# MySens-easyRS485-BluePill-V03-010.net
KiCad netlist of a schematic drawn in EAGLE
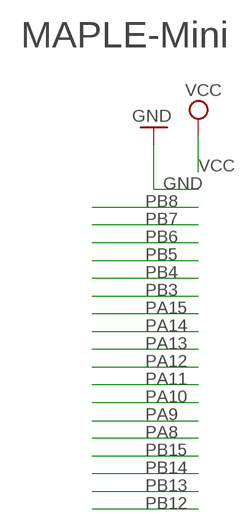
[diagram p0: schematic, sheet 1, part 1 of 2]
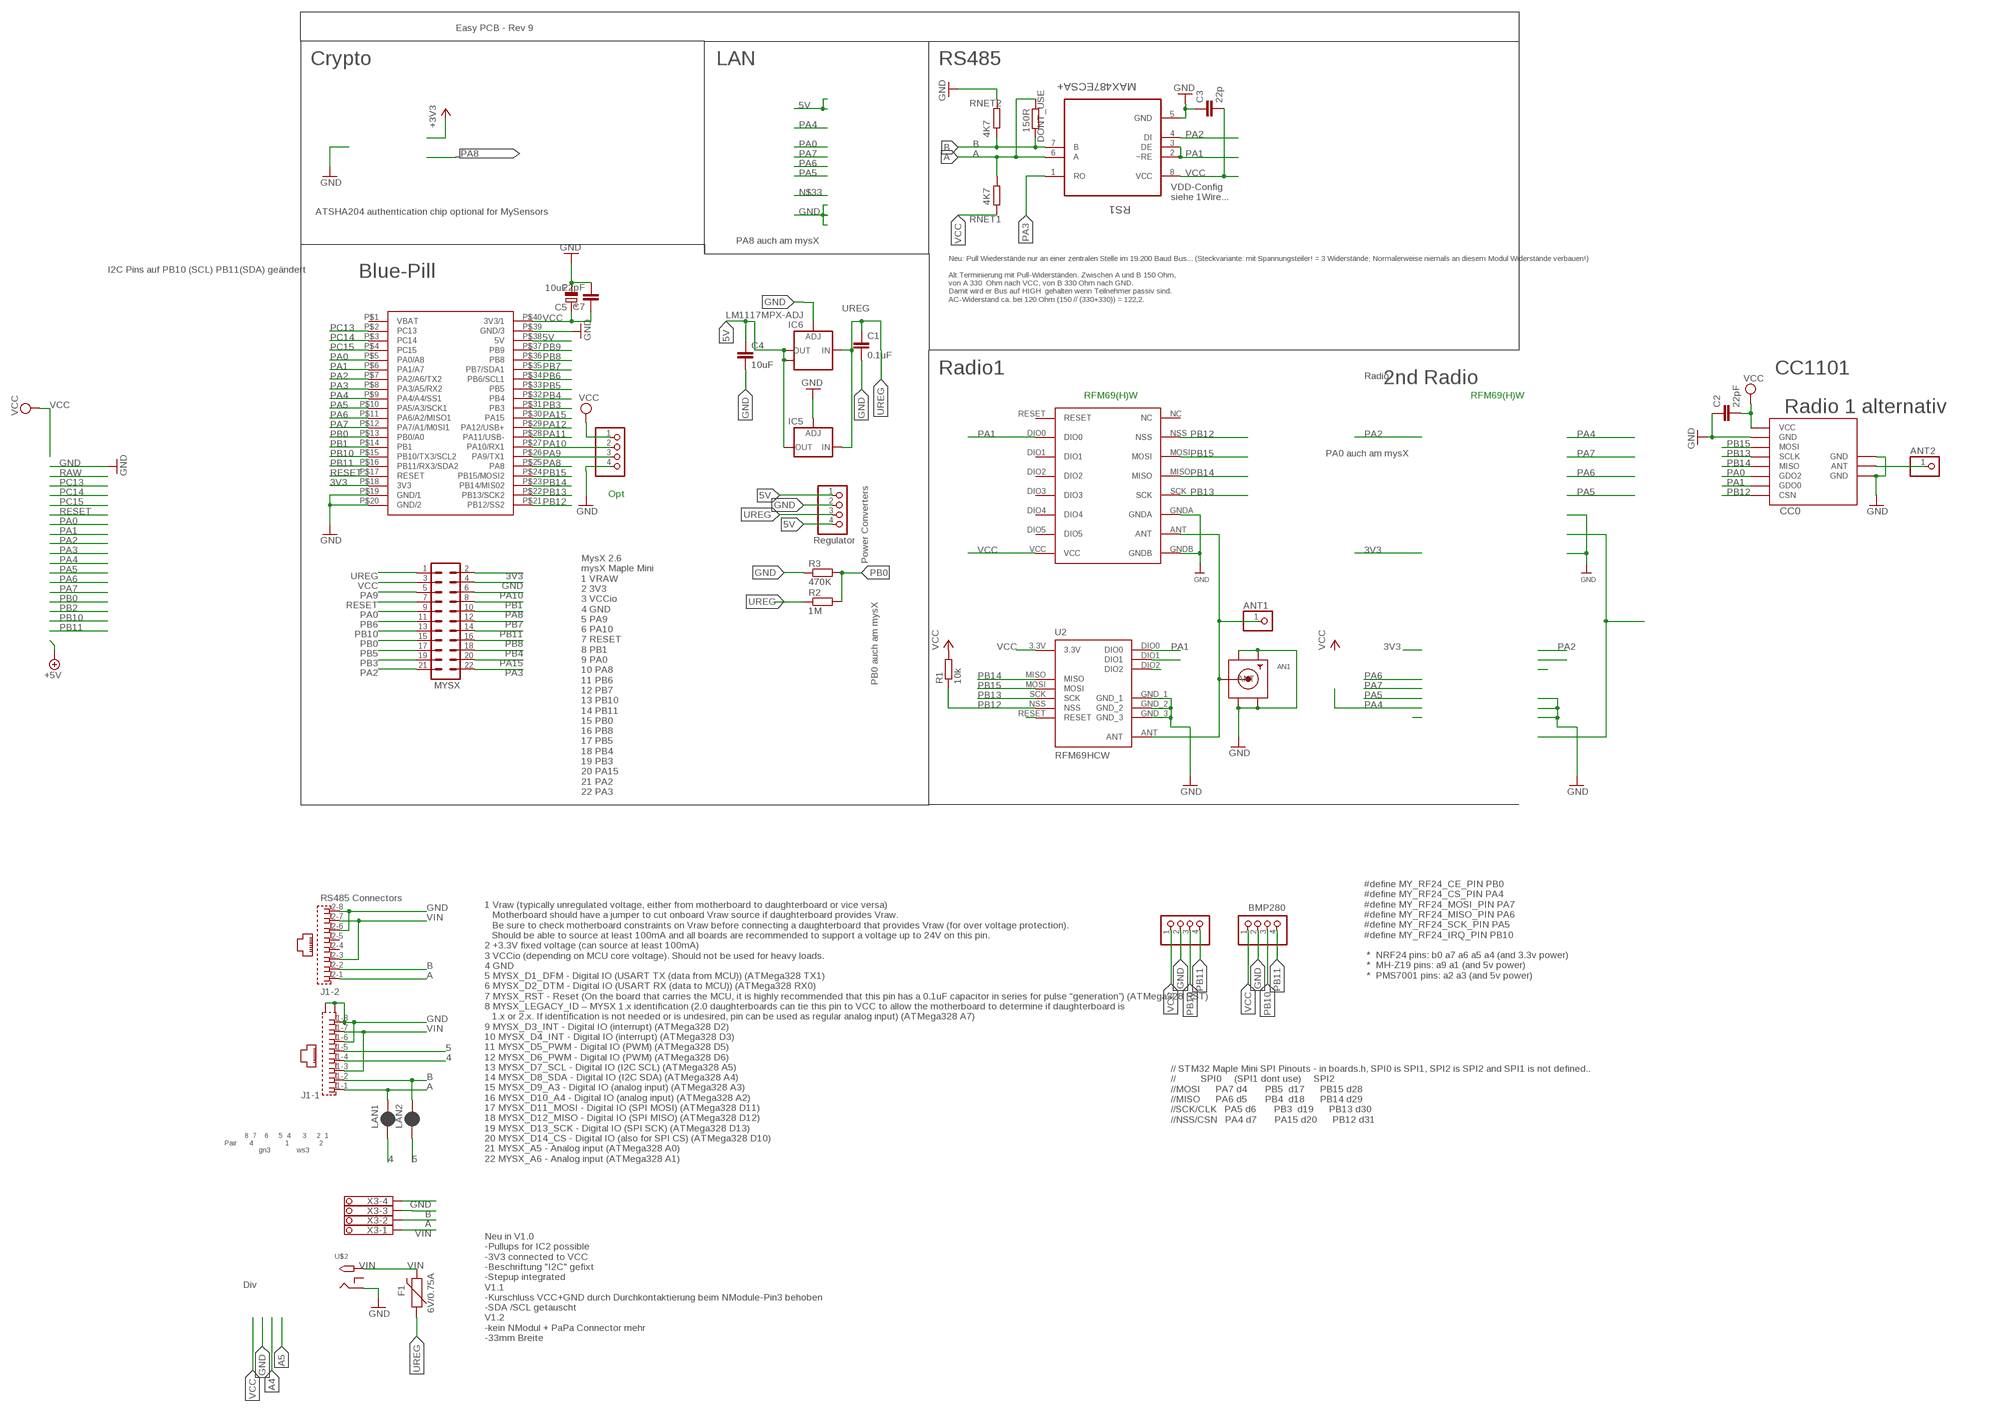
[diagram p1: schematic, sheet 1, part 2 of 2]

(export (version "E")
  (design (tool "Eeschema 10.0.6"))
  (components
    (comp (ref "AN1")
      (value "SMACONNECTOR_EDGE")
      (footprint "eagle-import:SMA_EDGELAUNCH")
      (libsource (lib "eagle-import") (part "SMACONNECTOR_EDGE"))
    )
    (comp (ref "ANT1")
      (value "PINHD-1X1")
      (footprint "eagle-import:1X01")
      (libsource (lib "eagle-import") (part "PINHD-1X1"))
    )
    (comp (ref "ANT2")
      (value "PINHD-1X1")
      (footprint "eagle-import:1X01")
      (libsource (lib "eagle-import") (part "PINHD-1X1"))
    )
    (comp (ref "BH1750")
      (value "PINHD-1X04_2.54-S")
      (footprint "eagle-import:1X04-S")
      (libsource (lib "eagle-import") (part "PINHD-1X04_2.54-S"))
    )
    (comp (ref "C1")
      (value "0.1uF")
      (footprint "eagle-import:C1206")
      (libsource (lib "eagle-import") (part "C-EUC1206"))
    )
    (comp (ref "C2")
      (value "22pF")
      (footprint "eagle-import:C0805")
      (libsource (lib "eagle-import") (part "C-EUC0805"))
    )
    (comp (ref "C3")
      (value "22p")
      (footprint "eagle-import:C0805")
      (libsource (lib "eagle-import") (part "C-EUC0805"))
    )
    (comp (ref "C4")
      (value "10uF")
      (footprint "eagle-import:C1210")
      (libsource (lib "eagle-import") (part "C-EUC1210"))
    )
    (comp (ref "C5")
      (value "10uF")
      (footprint "eagle-import:R_2012-12W")
      (libsource (lib "eagle-import") (part "CPOL-EUR/2012-12W"))
    )
    (comp (ref "C7")
      (value "22pF")
      (footprint "eagle-import:C0805")
      (libsource (lib "eagle-import") (part "C-EUC0805"))
    )
    (comp (ref "CC0")
      (value "CC1101")
      (footprint "eagle-import:CC1101_MODULE1_SMD")
      (libsource (lib "eagle-import") (part "CC1101_MODULE1SMD"))
    )
    (comp (ref "DBG")
      (value "PINHD-1X04_2.54-S")
      (footprint "eagle-import:1X04-S")
      (libsource (lib "eagle-import") (part "PINHD-1X04_2.54-S"))
    )
    (comp (ref "DONT_USE")
      (value "150R")
      (footprint "eagle-import:R0805")
      (libsource (lib "eagle-import") (part "R-EU_R0805"))
    )
    (comp (ref "F1")
      (value "6V/0.75A")
      (footprint "eagle-import:1206")
      (libsource (lib "eagle-import") (part "PPTC_THREE-QUARTER-AMP"))
    )
    (comp (ref "I2C-1")
      (value "PINHD-1X04_2.54-S")
      (footprint "eagle-import:1X04-S")
      (libsource (lib "eagle-import") (part "PINHD-1X04_2.54-S"))
    )
    (comp (ref "IC5")
      (value "LD117ADT50TR")
      (footprint "eagle-import:DPACK")
      (libsource (lib "eagle-import") (part "LD117A?DT50TR"))
    )
    (comp (ref "IC6")
      (value "LM1117MPX-ADJ")
      (footprint "eagle-import:SOT223")
      (libsource (lib "eagle-import") (part "LM1117MPX-ADJ"))
    )
    (comp (ref "J1")
      (value "RJ45_2X_S")
      (footprint "eagle-import:RJ45_2X_S")
      (libsource (lib "eagle-import") (part "RJ45_2X_S"))
    )
    (comp (ref "LAN1")
      (value "JUMPER-SMT_2_NC_PASTE_SILK")
      (footprint "eagle-import:SMT-JUMPER_2_NC_PASTE_SILK")
      (libsource (lib "eagle-import") (part "JUMPER-SMT_2_NC_PASTE_SILK"))
    )
    (comp (ref "LAN2")
      (value "JUMPER-SMT_2_NC_PASTE_SILK")
      (footprint "eagle-import:SMT-JUMPER_2_NC_PASTE_SILK")
      (libsource (lib "eagle-import") (part "JUMPER-SMT_2_NC_PASTE_SILK"))
    )
    (comp (ref "MYSX")
      (value "MA11-2")
      (footprint "eagle-import:MA11-2")
      (libsource (lib "eagle-import") (part "MA11-2"))
    )
    (comp (ref "R1")
      (value "10k")
      (footprint "eagle-import:M0805")
      (libsource (lib "eagle-import") (part "R-EU_M0805"))
    )
    (comp (ref "R2")
      (value "1M")
      (footprint "eagle-import:R0805")
      (libsource (lib "eagle-import") (part "R-EU_R0805"))
    )
    (comp (ref "R3")
      (value "470K")
      (footprint "eagle-import:R0805")
      (libsource (lib "eagle-import") (part "R-EU_R0805"))
    )
    (comp (ref "RFM69W1")
      (value "RFM69HW")
      (footprint "eagle-import:RFM")
      (libsource (lib "eagle-import") (part "RFM69HW"))
    )
    (comp (ref "RNET1")
      (value "4K7")
      (footprint "eagle-import:R0805")
      (libsource (lib "eagle-import") (part "R-EU_R0805"))
    )
    (comp (ref "RNET2")
      (value "4K7")
      (footprint "eagle-import:R0805")
      (libsource (lib "eagle-import") (part "R-EU_R0805"))
    )
    (comp (ref "RS1")
      (value "MAX487ECSA+")
      (footprint "eagle-import:SOIC127P600X175-8N")
      (libsource (lib "eagle-import") (part "MAX487ECSA+"))
    )
    (comp (ref "STEPDWN")
      (value "PINHD-1X04_2.54-S")
      (footprint "eagle-import:1X04-S")
      (libsource (lib "eagle-import") (part "PINHD-1X04_2.54-S"))
    )
    (comp (ref "U$2")
      (value "2.1MMJACKTHM")
      (footprint "eagle-import:PJ-102A")
      (libsource (lib "eagle-import") (part "2.1MMJACKTHM"))
    )
    (comp (ref "U$4")
      (value "BLUEPILL")
      (footprint "eagle-import:BLUEPILL")
      (libsource (lib "eagle-import") (part "BLUEPILL"))
    )
    (comp (ref "U2")
      (value "RFM69HCW")
      (footprint "eagle-import:RFM69HCW-XXXS2")
      (libsource (lib "eagle-import") (part "RFM69HCW"))
    )
    (comp (ref "X3")
      (value "1751264")
      (footprint "eagle-import:1751264")
      (libsource (lib "eagle-import") (part "1751264"))
    )
  )
  (nets
    (net (code "3") (name "/3V3") (class "Default")
      (node (ref "MYSX") (pin "2") (pinfunction "2_2") (pintype "passive"))
      (node (ref "U$4") (pin "P$18") (pinfunction "3V3_P$18") (pintype "bidirectional"))
    )
    (net (code "4") (name "/4") (class "Default")
      (node (ref "J1") (pin "1-4") (pinfunction "4_1-4") (pintype "passive"))
      (node (ref "LAN1") (pin "1") (pinfunction "1_1") (pintype "passive"))
    )
    (net (code "5") (name "/5") (class "Default")
      (node (ref "J1") (pin "1-5") (pinfunction "5_1-5") (pintype "passive"))
      (node (ref "LAN2") (pin "1") (pinfunction "1_1") (pintype "passive"))
    )
    (net (code "7") (name "/PA0") (class "Default")
      (node (ref "CC0") (pin "GDO2") (pinfunction "GDO2_GDO2") (pintype "bidirectional"))
      (node (ref "MYSX") (pin "9") (pinfunction "9_9") (pintype "passive"))
      (node (ref "U$4") (pin "P$5") (pinfunction "PA0/A8_P$5") (pintype "bidirectional"))
    )
    (net (code "8") (name "/PA1") (class "Default")
      (node (ref "CC0") (pin "GDO0") (pinfunction "GDO0_GDO0") (pintype "bidirectional"))
      (node (ref "RFM69W1") (pin "DIO0") (pinfunction "DIO0_DIO0") (pintype "bidirectional"))
      (node (ref "RS1") (pin "2") (pinfunction "~{RE}_2") (pintype "input"))
      (node (ref "RS1") (pin "3") (pinfunction "DE_3") (pintype "input"))
      (node (ref "U$4") (pin "P$6") (pinfunction "PA1/A7_P$6") (pintype "bidirectional"))
      (node (ref "U2") (pin "DIO0") (pinfunction "DIO0_DIO0") (pintype "bidirectional"))
    )
    (net (code "9") (name "/PA2") (class "Default")
      (node (ref "MYSX") (pin "21") (pinfunction "21_21") (pintype "passive"))
      (node (ref "RS1") (pin "4") (pinfunction "DI_4") (pintype "input"))
      (node (ref "U$4") (pin "P$7") (pinfunction "PA2/A6/TX2_P$7") (pintype "bidirectional"))
    )
    (net (code "10") (name "/PA4") (class "Default")
      (node (ref "U$4") (pin "P$9") (pinfunction "PA4/A4/SS1_P$9") (pintype "bidirectional"))
    )
    (net (code "11") (name "/PA5") (class "Default")
      (node (ref "U$4") (pin "P$10") (pinfunction "PA5/A3/SCK1_P$10") (pintype "bidirectional"))
    )
    (net (code "12") (name "/PA6") (class "Default")
      (node (ref "U$4") (pin "P$11") (pinfunction "PA6/A2/MISO1_P$11") (pintype "bidirectional"))
    )
    (net (code "13") (name "/PA7") (class "Default")
      (node (ref "U$4") (pin "P$12") (pinfunction "PA7/A1/M0SI1_P$12") (pintype "bidirectional"))
    )
    (net (code "14") (name "/PA8") (class "Default")
      (node (ref "MYSX") (pin "10") (pinfunction "10_10") (pintype "passive"))
      (node (ref "U$4") (pin "P$25") (pinfunction "PA8_P$25") (pintype "bidirectional"))
    )
    (net (code "15") (name "/PA9") (class "Default")
      (node (ref "DBG") (pin "3") (pinfunction "3_3") (pintype "passive"))
      (node (ref "MYSX") (pin "5") (pinfunction "5_5") (pintype "passive"))
      (node (ref "U$4") (pin "P$26") (pinfunction "PA9/TX1_P$26") (pintype "bidirectional"))
    )
    (net (code "16") (name "/PA10") (class "Default")
      (node (ref "DBG") (pin "2") (pinfunction "2_2") (pintype "passive"))
      (node (ref "MYSX") (pin "6") (pinfunction "6_6") (pintype "passive"))
      (node (ref "U$4") (pin "P$27") (pinfunction "PA10/RX1_P$27") (pintype "bidirectional"))
    )
    (net (code "17") (name "/PA11") (class "Default")
      (node (ref "U$4") (pin "P$28") (pinfunction "PA11/USB-_P$28") (pintype "bidirectional"))
    )
    (net (code "18") (name "/PA12") (class "Default")
      (node (ref "U$4") (pin "P$29") (pinfunction "PA12/USB+_P$29") (pintype "bidirectional"))
    )
    (net (code "21") (name "/PA15") (class "Default")
      (node (ref "MYSX") (pin "20") (pinfunction "20_20") (pintype "passive"))
      (node (ref "U$4") (pin "P$30") (pinfunction "PA15_P$30") (pintype "bidirectional"))
    )
    (net (code "22") (name "/PB1") (class "Default")
      (node (ref "MYSX") (pin "8") (pinfunction "8_8") (pintype "passive"))
      (node (ref "U$4") (pin "P$14") (pinfunction "PB1_P$14") (pintype "bidirectional"))
    )
    (net (code "24") (name "/PB3") (class "Default")
      (node (ref "MYSX") (pin "19") (pinfunction "19_19") (pintype "passive"))
      (node (ref "U$4") (pin "P$31") (pinfunction "PB3_P$31") (pintype "bidirectional"))
    )
    (net (code "25") (name "/PB4") (class "Default")
      (node (ref "MYSX") (pin "18") (pinfunction "18_18") (pintype "passive"))
      (node (ref "U$4") (pin "P$32") (pinfunction "PB4_P$32") (pintype "bidirectional"))
    )
    (net (code "26") (name "/PB5") (class "Default")
      (node (ref "MYSX") (pin "17") (pinfunction "17_17") (pintype "passive"))
      (node (ref "U$4") (pin "P$33") (pinfunction "PB5_P$33") (pintype "bidirectional"))
    )
    (net (code "27") (name "/PB6") (class "Default")
      (node (ref "MYSX") (pin "11") (pinfunction "11_11") (pintype "passive"))
      (node (ref "U$4") (pin "P$34") (pinfunction "PB6/SCL1_P$34") (pintype "bidirectional"))
    )
    (net (code "28") (name "/PB7") (class "Default")
      (node (ref "MYSX") (pin "12") (pinfunction "12_12") (pintype "passive"))
      (node (ref "U$4") (pin "P$35") (pinfunction "PB7/SDA1_P$35") (pintype "bidirectional"))
    )
    (net (code "29") (name "/PB8") (class "Default")
      (node (ref "MYSX") (pin "16") (pinfunction "16_16") (pintype "passive"))
      (node (ref "U$4") (pin "P$36") (pinfunction "PB8_P$36") (pintype "bidirectional"))
    )
    (net (code "30") (name "/PB9") (class "Default")
      (node (ref "U$4") (pin "P$37") (pinfunction "PB9_P$37") (pintype "bidirectional"))
    )
    (net (code "31") (name "/PB12") (class "Default")
      (node (ref "CC0") (pin "CSN") (pinfunction "CSN_CSN") (pintype "bidirectional"))
      (node (ref "R1") (pin "1") (pinfunction "1_1") (pintype "passive"))
      (node (ref "RFM69W1") (pin "NSS") (pinfunction "NSS_NSS") (pintype "bidirectional"))
      (node (ref "U$4") (pin "P$21") (pinfunction "PB12/SS2_P$21") (pintype "bidirectional"))
      (node (ref "U2") (pin "NSS") (pinfunction "NSS_NSS") (pintype "input"))
    )
    (net (code "32") (name "/PB13") (class "Default")
      (node (ref "CC0") (pin "SCLK") (pinfunction "SCLK_SCLK") (pintype "bidirectional"))
      (node (ref "RFM69W1") (pin "SCK") (pinfunction "SCK_SCK") (pintype "bidirectional"))
      (node (ref "U$4") (pin "P$22") (pinfunction "PB13/SCK2_P$22") (pintype "bidirectional"))
      (node (ref "U2") (pin "SCK") (pinfunction "SCK_SCK") (pintype "input"))
    )
    (net (code "33") (name "/PB14") (class "Default")
      (node (ref "CC0") (pin "MISO") (pinfunction "MISO_MISO") (pintype "bidirectional"))
      (node (ref "RFM69W1") (pin "MISO") (pinfunction "MISO_MISO") (pintype "bidirectional"))
      (node (ref "U$4") (pin "P$23") (pinfunction "PB14/MIS02_P$23") (pintype "bidirectional"))
      (node (ref "U2") (pin "MISO") (pinfunction "MISO_MISO") (pintype "bidirectional"))
    )
    (net (code "34") (name "/PB15") (class "Default")
      (node (ref "CC0") (pin "MOSI") (pinfunction "MOSI_MOSI") (pintype "bidirectional"))
      (node (ref "RFM69W1") (pin "MOSI") (pinfunction "MOSI_MOSI") (pintype "bidirectional"))
      (node (ref "U$4") (pin "P$24") (pinfunction "PB15/MOSI2_P$24") (pintype "bidirectional"))
      (node (ref "U2") (pin "MOSI") (pinfunction "MOSI_MOSI") (pintype "input"))
    )
    (net (code "35") (name "/PC13") (class "Default")
      (node (ref "U$4") (pin "P$2") (pinfunction "PC13_P$2") (pintype "bidirectional"))
    )
    (net (code "36") (name "/PC14") (class "Default")
      (node (ref "U$4") (pin "P$3") (pinfunction "PC14_P$3") (pintype "bidirectional"))
    )
    (net (code "37") (name "/PC15") (class "Default")
      (node (ref "U$4") (pin "P$4") (pinfunction "PC15_P$4") (pintype "bidirectional"))
    )
    (net (code "39") (name "/RESET") (class "Default")
      (node (ref "MYSX") (pin "7") (pinfunction "7_7") (pintype "passive"))
      (node (ref "U$4") (pin "P$17") (pinfunction "RESET_P$17") (pintype "bidirectional"))
    )
    (net (code "40") (name "/VIN") (class "Default")
      (node (ref "F1") (pin "2") (pinfunction "2_2") (pintype "bidirectional"))
      (node (ref "J1") (pin "1-3") (pinfunction "3_1-3") (pintype "passive"))
      (node (ref "J1") (pin "1-7") (pinfunction "7_1-7") (pintype "passive"))
      (node (ref "J1") (pin "2-3") (pinfunction "3_2-3") (pintype "passive"))
      (node (ref "J1") (pin "2-7") (pinfunction "7_2-7") (pintype "passive"))
      (node (ref "U$2") (pin "TIP") (pinfunction "TIP_TIP") (pintype "bidirectional"))
      (node (ref "X3") (pin "1") (pinfunction "K_1") (pintype "passive"))
    )
    (net (code "41") (name "5V") (class "Default")
      (node (ref "C4") (pin "1") (pinfunction "1_1") (pintype "passive"))
      (node (ref "IC5") (pin "4") (pinfunction "OUT_4") (pintype "passive"))
      (node (ref "IC6") (pin "2") (pinfunction "OUT_2") (pintype "passive"))
      (node (ref "IC6") (pin "TAB") (pinfunction "OUT1_TAB") (pintype "passive"))
      (node (ref "STEPDWN") (pin "1") (pinfunction "1_1") (pintype "passive"))
      (node (ref "STEPDWN") (pin "4") (pinfunction "4_4") (pintype "passive"))
      (node (ref "U$4") (pin "P$38") (pinfunction "5V_P$38") (pintype "bidirectional"))
    )
    (net (code "42") (name "A") (class "Default")
      (node (ref "DONT_USE") (pin "1") (pinfunction "1_1") (pintype "passive"))
      (node (ref "J1") (pin "1-1") (pinfunction "1_1-1") (pintype "passive"))
      (node (ref "J1") (pin "2-1") (pinfunction "1_2-1") (pintype "passive"))
      (node (ref "LAN1") (pin "2") (pinfunction "2_2") (pintype "passive"))
      (node (ref "RNET1") (pin "2") (pinfunction "2_2") (pintype "passive"))
      (node (ref "RS1") (pin "6") (pinfunction "A_6") (pintype "bidirectional"))
      (node (ref "X3") (pin "2") (pinfunction "K_2") (pintype "passive"))
    )
    (net (code "45") (name "B") (class "Default")
      (node (ref "DONT_USE") (pin "2") (pinfunction "2_2") (pintype "passive"))
      (node (ref "J1") (pin "1-2") (pinfunction "2_1-2") (pintype "passive"))
      (node (ref "J1") (pin "2-2") (pinfunction "2_2-2") (pintype "passive"))
      (node (ref "LAN2") (pin "2") (pinfunction "2_2") (pintype "passive"))
      (node (ref "RNET2") (pin "1") (pinfunction "1_1") (pintype "passive"))
      (node (ref "RS1") (pin "7") (pinfunction "B_7") (pintype "bidirectional"))
      (node (ref "X3") (pin "3") (pinfunction "K_3") (pintype "passive"))
    )
    (net (code "46") (name "GND") (class "Default")
      (node (ref "AN1") (pin "GND@1") (pinfunction "GND4_GND@1") (pintype "power_in"))
      (node (ref "AN1") (pin "GND@2") (pinfunction "GND3_GND@2") (pintype "power_in"))
      (node (ref "AN1") (pin "GND@3") (pinfunction "GND2_GND@3") (pintype "power_in"))
      (node (ref "AN1") (pin "GND@4") (pinfunction "GND1_GND@4") (pintype "power_in"))
      (node (ref "BH1750") (pin "2") (pinfunction "2_2") (pintype "passive"))
      (node (ref "C1") (pin "2") (pinfunction "2_2") (pintype "passive"))
      (node (ref "C2") (pin "1") (pinfunction "1_1") (pintype "passive"))
      (node (ref "C3") (pin "1") (pinfunction "1_1") (pintype "passive"))
      (node (ref "C4") (pin "2") (pinfunction "2_2") (pintype "passive"))
      (node (ref "C5") (pin "-") (pinfunction "-_-") (pintype "passive"))
      (node (ref "C7") (pin "2") (pinfunction "2_2") (pintype "passive"))
      (node (ref "CC0") (pin "GND@0") (pinfunction "GND_GND@0") (pintype "power_in"))
      (node (ref "CC0") (pin "GND@1") (pinfunction "GND_GND@1") (pintype "power_in"))
      (node (ref "CC0") (pin "GND@2") (pinfunction "GND_GND@2") (pintype "power_in"))
      (node (ref "DBG") (pin "4") (pinfunction "4_4") (pintype "passive"))
      (node (ref "I2C-1") (pin "2") (pinfunction "2_2") (pintype "passive"))
      (node (ref "IC5") (pin "1") (pinfunction "ADJ_1") (pintype "input"))
      (node (ref "IC6") (pin "1") (pinfunction "ADJ_1") (pintype "input"))
      (node (ref "J1") (pin "1-6") (pinfunction "6_1-6") (pintype "passive"))
      (node (ref "J1") (pin "1-8") (pinfunction "8_1-8") (pintype "passive"))
      (node (ref "J1") (pin "2-6") (pinfunction "6_2-6") (pintype "passive"))
      (node (ref "J1") (pin "2-8") (pinfunction "8_2-8") (pintype "passive"))
      (node (ref "J1") (pin "G1") (pinfunction "S2_G1") (pintype "passive"))
      (node (ref "J1") (pin "G3") (pinfunction "S1_G3") (pintype "passive"))
      (node (ref "MYSX") (pin "4") (pinfunction "4_4") (pintype "passive"))
      (node (ref "R3") (pin "1") (pinfunction "1_1") (pintype "passive"))
      (node (ref "RFM69W1") (pin "GNDA") (pinfunction "GNDA_GNDA") (pintype "bidirectional"))
      (node (ref "RFM69W1") (pin "GNDB") (pinfunction "GNDB_GNDB") (pintype "bidirectional"))
      (node (ref "RNET2") (pin "2") (pinfunction "2_2") (pintype "passive"))
      (node (ref "RS1") (pin "5") (pinfunction "GND_5") (pintype "passive"))
      (node (ref "STEPDWN") (pin "2") (pinfunction "2_2") (pintype "passive"))
      (node (ref "U$2") (pin "RING") (pinfunction "RING_RING") (pintype "bidirectional"))
      (node (ref "U$4") (pin "P$19") (pinfunction "GND/1_P$19") (pintype "bidirectional"))
      (node (ref "U$4") (pin "P$20") (pinfunction "GND/2_P$20") (pintype "bidirectional"))
      (node (ref "U$4") (pin "P$39") (pinfunction "GND/3_P$39") (pintype "bidirectional"))
      (node (ref "U2") (pin "GND_1") (pinfunction "GND_1_GND_1") (pintype "power_in"))
      (node (ref "U2") (pin "GND_2") (pinfunction "GND_2_GND_2") (pintype "power_in"))
      (node (ref "U2") (pin "GND_3") (pinfunction "GND_3_GND_3") (pintype "power_in"))
      (node (ref "X3") (pin "4") (pinfunction "K_4") (pintype "passive"))
    )
    (net (code "47") (name "Net-(AN1-ANT)") (class "Default")
      (node (ref "AN1") (pin "P") (pinfunction "ANT_P") (pintype "bidirectional"))
      (node (ref "ANT1") (pin "1") (pinfunction "1_1") (pintype "passive"))
      (node (ref "RFM69W1") (pin "ANT") (pinfunction "ANT_ANT") (pintype "bidirectional"))
      (node (ref "U2") (pin "ANT") (pinfunction "ANT_ANT") (pintype "passive"))
    )
    (net (code "48") (name "Net-(ANT2-Pad1)") (class "Default")
      (node (ref "ANT2") (pin "1") (pinfunction "1_1") (pintype "passive"))
      (node (ref "CC0") (pin "ANT") (pinfunction "ANT_ANT") (pintype "output"))
    )
    (net (code "49") (name "PA3") (class "Default")
      (node (ref "MYSX") (pin "22") (pinfunction "22_22") (pintype "passive"))
      (node (ref "RS1") (pin "1") (pinfunction "RO_1") (pintype "output"))
      (node (ref "U$4") (pin "P$8") (pinfunction "PA3/A5/RX2_P$8") (pintype "bidirectional"))
    )
    (net (code "50") (name "PB0") (class "Default")
      (node (ref "MYSX") (pin "15") (pinfunction "15_15") (pintype "passive"))
      (node (ref "R2") (pin "2") (pinfunction "2_2") (pintype "passive"))
      (node (ref "R3") (pin "2") (pinfunction "2_2") (pintype "passive"))
      (node (ref "U$4") (pin "P$13") (pinfunction "PB0/A0_P$13") (pintype "bidirectional"))
    )
    (net (code "51") (name "PB10") (class "Default")
      (node (ref "BH1750") (pin "3") (pinfunction "3_3") (pintype "passive"))
      (node (ref "I2C-1") (pin "3") (pinfunction "3_3") (pintype "passive"))
      (node (ref "MYSX") (pin "13") (pinfunction "13_13") (pintype "passive"))
      (node (ref "U$4") (pin "P$15") (pinfunction "PB10/TX3/SCL2_P$15") (pintype "bidirectional"))
    )
    (net (code "52") (name "PB11") (class "Default")
      (node (ref "BH1750") (pin "4") (pinfunction "4_4") (pintype "passive"))
      (node (ref "I2C-1") (pin "4") (pinfunction "4_4") (pintype "passive"))
      (node (ref "MYSX") (pin "14") (pinfunction "14_14") (pintype "passive"))
      (node (ref "U$4") (pin "P$16") (pinfunction "PB11/RX3/SDA2_P$16") (pintype "bidirectional"))
    )
    (net (code "53") (name "UREG") (class "Default")
      (node (ref "C1") (pin "1") (pinfunction "1_1") (pintype "passive"))
      (node (ref "F1") (pin "1") (pinfunction "1_1") (pintype "bidirectional"))
      (node (ref "IC5") (pin "3") (pinfunction "IN_3") (pintype "input"))
      (node (ref "IC6") (pin "3") (pinfunction "IN_3") (pintype "input"))
      (node (ref "MYSX") (pin "1") (pinfunction "1_1") (pintype "passive"))
      (node (ref "R2") (pin "1") (pinfunction "1_1") (pintype "passive"))
      (node (ref "STEPDWN") (pin "3") (pinfunction "3_3") (pintype "passive"))
    )
    (net (code "54") (name "VCC") (class "Default")
      (node (ref "BH1750") (pin "1") (pinfunction "1_1") (pintype "passive"))
      (node (ref "C2") (pin "2") (pinfunction "2_2") (pintype "passive"))
      (node (ref "C3") (pin "2") (pinfunction "2_2") (pintype "passive"))
      (node (ref "C5") (pin "+") (pinfunction "+_+") (pintype "passive"))
      (node (ref "C7") (pin "1") (pinfunction "1_1") (pintype "passive"))
      (node (ref "CC0") (pin "VCC") (pinfunction "VCC_VCC") (pintype "power_in"))
      (node (ref "DBG") (pin "1") (pinfunction "1_1") (pintype "passive"))
      (node (ref "I2C-1") (pin "1") (pinfunction "1_1") (pintype "passive"))
      (node (ref "MYSX") (pin "3") (pinfunction "3_3") (pintype "passive"))
      (node (ref "R1") (pin "2") (pinfunction "2_2") (pintype "passive"))
      (node (ref "RFM69W1") (pin "VCC") (pinfunction "VCC_VCC") (pintype "bidirectional"))
      (node (ref "RNET1") (pin "1") (pinfunction "1_1") (pintype "passive"))
      (node (ref "RS1") (pin "8") (pinfunction "VCC_8") (pintype "power_in"))
      (node (ref "U$4") (pin "P$40") (pinfunction "3V3/1_P$40") (pintype "bidirectional"))
      (node (ref "U2") (pin "3.3V") (pinfunction "3.3V_3.3V") (pintype "power_in"))
    )
    (net (code "55") (name "unconnected-(J1B-4-Pad2-4)") (class "Default")
      (node (ref "J1") (pin "2-4") (pinfunction "4_2-4") (pintype "passive"))
    )
    (net (code "56") (name "unconnected-(J1B-5-Pad2-5)") (class "Default")
      (node (ref "J1") (pin "2-5") (pinfunction "5_2-5") (pintype "passive"))
    )
    (net (code "57") (name "unconnected-(RFM69W1-PadDIO1)") (class "Default")
      (node (ref "RFM69W1") (pin "DIO1") (pinfunction "DIO1_DIO1") (pintype "bidirectional"))
    )
    (net (code "58") (name "unconnected-(RFM69W1-PadDIO2)") (class "Default")
      (node (ref "RFM69W1") (pin "DIO2") (pinfunction "DIO2_DIO2") (pintype "bidirectional"))
    )
    (net (code "59") (name "unconnected-(RFM69W1-PadDIO3)") (class "Default")
      (node (ref "RFM69W1") (pin "DIO3") (pinfunction "DIO3_DIO3") (pintype "bidirectional"))
    )
    (net (code "60") (name "unconnected-(RFM69W1-PadDIO4)") (class "Default")
      (node (ref "RFM69W1") (pin "DIO4") (pinfunction "DIO4_DIO4") (pintype "bidirectional"))
    )
    (net (code "61") (name "unconnected-(RFM69W1-PadDIO5)") (class "Default")
      (node (ref "RFM69W1") (pin "DIO5") (pinfunction "DIO5_DIO5") (pintype "bidirectional"))
    )
    (net (code "62") (name "unconnected-(RFM69W1-PadNC)") (class "Default")
      (node (ref "RFM69W1") (pin "NC") (pinfunction "NC_NC") (pintype "bidirectional"))
    )
    (net (code "63") (name "unconnected-(RFM69W1-PadRESET)") (class "Default")
      (node (ref "RFM69W1") (pin "RESET") (pinfunction "RESET_RESET") (pintype "bidirectional"))
    )
    (net (code "64") (name "unconnected-(U$2-PadRING_SW)") (class "Default")
      (node (ref "U$2") (pin "RING_SW") (pinfunction "RING_SW_RING_SW") (pintype "bidirectional"))
    )
    (net (code "65") (name "unconnected-(U$4-VBAT-PadP$1)") (class "Default")
      (node (ref "U$4") (pin "P$1") (pinfunction "VBAT_P$1") (pintype "bidirectional"))
    )
    (net (code "66") (name "unconnected-(U2-PadDIO1)") (class "Default")
      (node (ref "U2") (pin "DIO1") (pinfunction "DIO1_DIO1") (pintype "bidirectional"))
    )
    (net (code "67") (name "unconnected-(U2-PadDIO2)") (class "Default")
      (node (ref "U2") (pin "DIO2") (pinfunction "DIO2_DIO2") (pintype "bidirectional"))
    )
    (net (code "68") (name "unconnected-(U2-PadRESET)") (class "Default")
      (node (ref "U2") (pin "RESET") (pinfunction "RESET_RESET") (pintype "input"))
    )
  )
)
